# 8CH-Level-Shifter.net
KiCad netlist of a schematic drawn in EAGLE
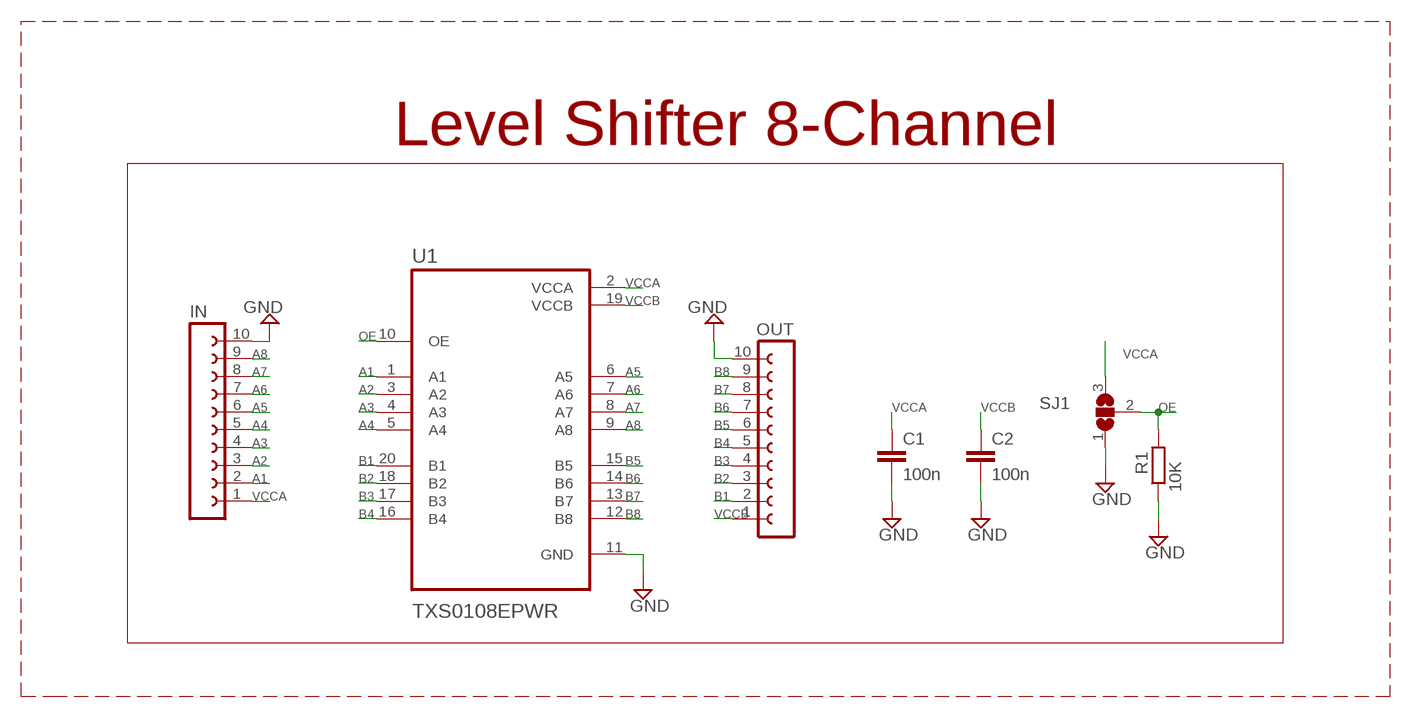
[diagram p0: schematic, sheet 1]

(export (version "E")
  (design (tool "Eeschema 10.0.6"))
  (components
    (comp (ref "C1")
      (value "100n")
      (footprint "eagle-import:C0805")
      (libsource (lib "eagle-import") (part "C-EUC0805"))
    )
    (comp (ref "C2")
      (value "100n")
      (footprint "eagle-import:C0805")
      (libsource (lib "eagle-import") (part "C-EUC0805"))
    )
    (comp (ref "IN")
      (value "CON-LSTA_FE10-1")
      (footprint "eagle-import:CON-LSTA_FE10")
      (libsource (lib "eagle-import") (part "CON-LSTA_FE10-1"))
    )
    (comp (ref "OUT")
      (value "CON-LSTA_FE10-1")
      (footprint "eagle-import:CON-LSTA_FE10")
      (libsource (lib "eagle-import") (part "CON-LSTA_FE10-1"))
    )
    (comp (ref "R1")
      (value "10K")
      (footprint "eagle-import:R0805")
      (libsource (lib "eagle-import") (part "R-EU_R0805"))
    )
    (comp (ref "SJ1")
      (value "SJ2W")
      (footprint "eagle-import:SJ_2")
      (libsource (lib "eagle-import") (part "SJ2W"))
    )
    (comp (ref "U1")
      (value "TXS0108EPWR")
      (footprint "eagle-import:SOP65P640X120-20N")
      (fields (field (name "MF") "Texas Instruments"))
      (libsource (lib "eagle-import") (part "TXS0108EPWR"))
    )
  )
  (nets
    (net (code "1") (name "/A1") (class "Default")
      (node (ref "IN") (pin "2") (pinfunction "2_2") (pintype "passive"))
      (node (ref "U1") (pin "1") (pinfunction "A1_1") (pintype "bidirectional"))
    )
    (net (code "2") (name "/A2") (class "Default")
      (node (ref "IN") (pin "3") (pinfunction "3_3") (pintype "passive"))
      (node (ref "U1") (pin "3") (pinfunction "A2_3") (pintype "bidirectional"))
    )
    (net (code "3") (name "/A3") (class "Default")
      (node (ref "IN") (pin "4") (pinfunction "4_4") (pintype "passive"))
      (node (ref "U1") (pin "4") (pinfunction "A3_4") (pintype "bidirectional"))
    )
    (net (code "4") (name "/A4") (class "Default")
      (node (ref "IN") (pin "5") (pinfunction "5_5") (pintype "passive"))
      (node (ref "U1") (pin "5") (pinfunction "A4_5") (pintype "bidirectional"))
    )
    (net (code "5") (name "/A5") (class "Default")
      (node (ref "IN") (pin "6") (pinfunction "6_6") (pintype "passive"))
      (node (ref "U1") (pin "6") (pinfunction "A5_6") (pintype "bidirectional"))
    )
    (net (code "6") (name "/A6") (class "Default")
      (node (ref "IN") (pin "7") (pinfunction "7_7") (pintype "passive"))
      (node (ref "U1") (pin "7") (pinfunction "A6_7") (pintype "bidirectional"))
    )
    (net (code "7") (name "/A7") (class "Default")
      (node (ref "IN") (pin "8") (pinfunction "8_8") (pintype "passive"))
      (node (ref "U1") (pin "8") (pinfunction "A7_8") (pintype "bidirectional"))
    )
    (net (code "8") (name "/A8") (class "Default")
      (node (ref "IN") (pin "9") (pinfunction "9_9") (pintype "passive"))
      (node (ref "U1") (pin "9") (pinfunction "A8_9") (pintype "bidirectional"))
    )
    (net (code "9") (name "/B1") (class "Default")
      (node (ref "OUT") (pin "2") (pinfunction "2_2") (pintype "passive"))
      (node (ref "U1") (pin "20") (pinfunction "B1_20") (pintype "bidirectional"))
    )
    (net (code "10") (name "/B2") (class "Default")
      (node (ref "OUT") (pin "3") (pinfunction "3_3") (pintype "passive"))
      (node (ref "U1") (pin "18") (pinfunction "B2_18") (pintype "bidirectional"))
    )
    (net (code "11") (name "/B3") (class "Default")
      (node (ref "OUT") (pin "4") (pinfunction "4_4") (pintype "passive"))
      (node (ref "U1") (pin "17") (pinfunction "B3_17") (pintype "bidirectional"))
    )
    (net (code "12") (name "/B4") (class "Default")
      (node (ref "OUT") (pin "5") (pinfunction "5_5") (pintype "passive"))
      (node (ref "U1") (pin "16") (pinfunction "B4_16") (pintype "bidirectional"))
    )
    (net (code "13") (name "/B5") (class "Default")
      (node (ref "OUT") (pin "6") (pinfunction "6_6") (pintype "passive"))
      (node (ref "U1") (pin "15") (pinfunction "B5_15") (pintype "bidirectional"))
    )
    (net (code "14") (name "/B6") (class "Default")
      (node (ref "OUT") (pin "7") (pinfunction "7_7") (pintype "passive"))
      (node (ref "U1") (pin "14") (pinfunction "B6_14") (pintype "bidirectional"))
    )
    (net (code "15") (name "/B7") (class "Default")
      (node (ref "OUT") (pin "8") (pinfunction "8_8") (pintype "passive"))
      (node (ref "U1") (pin "13") (pinfunction "B7_13") (pintype "bidirectional"))
    )
    (net (code "16") (name "/B8") (class "Default")
      (node (ref "OUT") (pin "9") (pinfunction "9_9") (pintype "passive"))
      (node (ref "U1") (pin "12") (pinfunction "B8_12") (pintype "bidirectional"))
    )
    (net (code "17") (name "/OE") (class "Default")
      (node (ref "R1") (pin "2") (pinfunction "2_2") (pintype "passive"))
      (node (ref "SJ1") (pin "2") (pinfunction "2_2") (pintype "passive"))
      (node (ref "U1") (pin "10") (pinfunction "OE_10") (pintype "input"))
    )
    (net (code "18") (name "/VCCA") (class "Default")
      (node (ref "C1") (pin "1") (pinfunction "1_1") (pintype "passive"))
      (node (ref "IN") (pin "1") (pinfunction "1_1") (pintype "passive"))
      (node (ref "SJ1") (pin "3") (pinfunction "3_3") (pintype "passive"))
      (node (ref "U1") (pin "2") (pinfunction "VCCA_2") (pintype "power_in"))
    )
    (net (code "19") (name "/VCCB") (class "Default")
      (node (ref "C2") (pin "1") (pinfunction "1_1") (pintype "passive"))
      (node (ref "OUT") (pin "1") (pinfunction "1_1") (pintype "passive"))
      (node (ref "U1") (pin "19") (pinfunction "VCCB_19") (pintype "power_in"))
    )
    (net (code "20") (name "GND") (class "Default")
      (node (ref "C1") (pin "2") (pinfunction "2_2") (pintype "passive"))
      (node (ref "C2") (pin "2") (pinfunction "2_2") (pintype "passive"))
      (node (ref "IN") (pin "10") (pinfunction "10_10") (pintype "passive"))
      (node (ref "OUT") (pin "10") (pinfunction "10_10") (pintype "passive"))
      (node (ref "R1") (pin "1") (pinfunction "1_1") (pintype "passive"))
      (node (ref "SJ1") (pin "1") (pinfunction "1_1") (pintype "passive"))
      (node (ref "U1") (pin "11") (pinfunction "GND_11") (pintype "power_in"))
    )
  )
)
